# mix2_LO2.net
KiCad netlist of a schematic drawn in Altium Designer
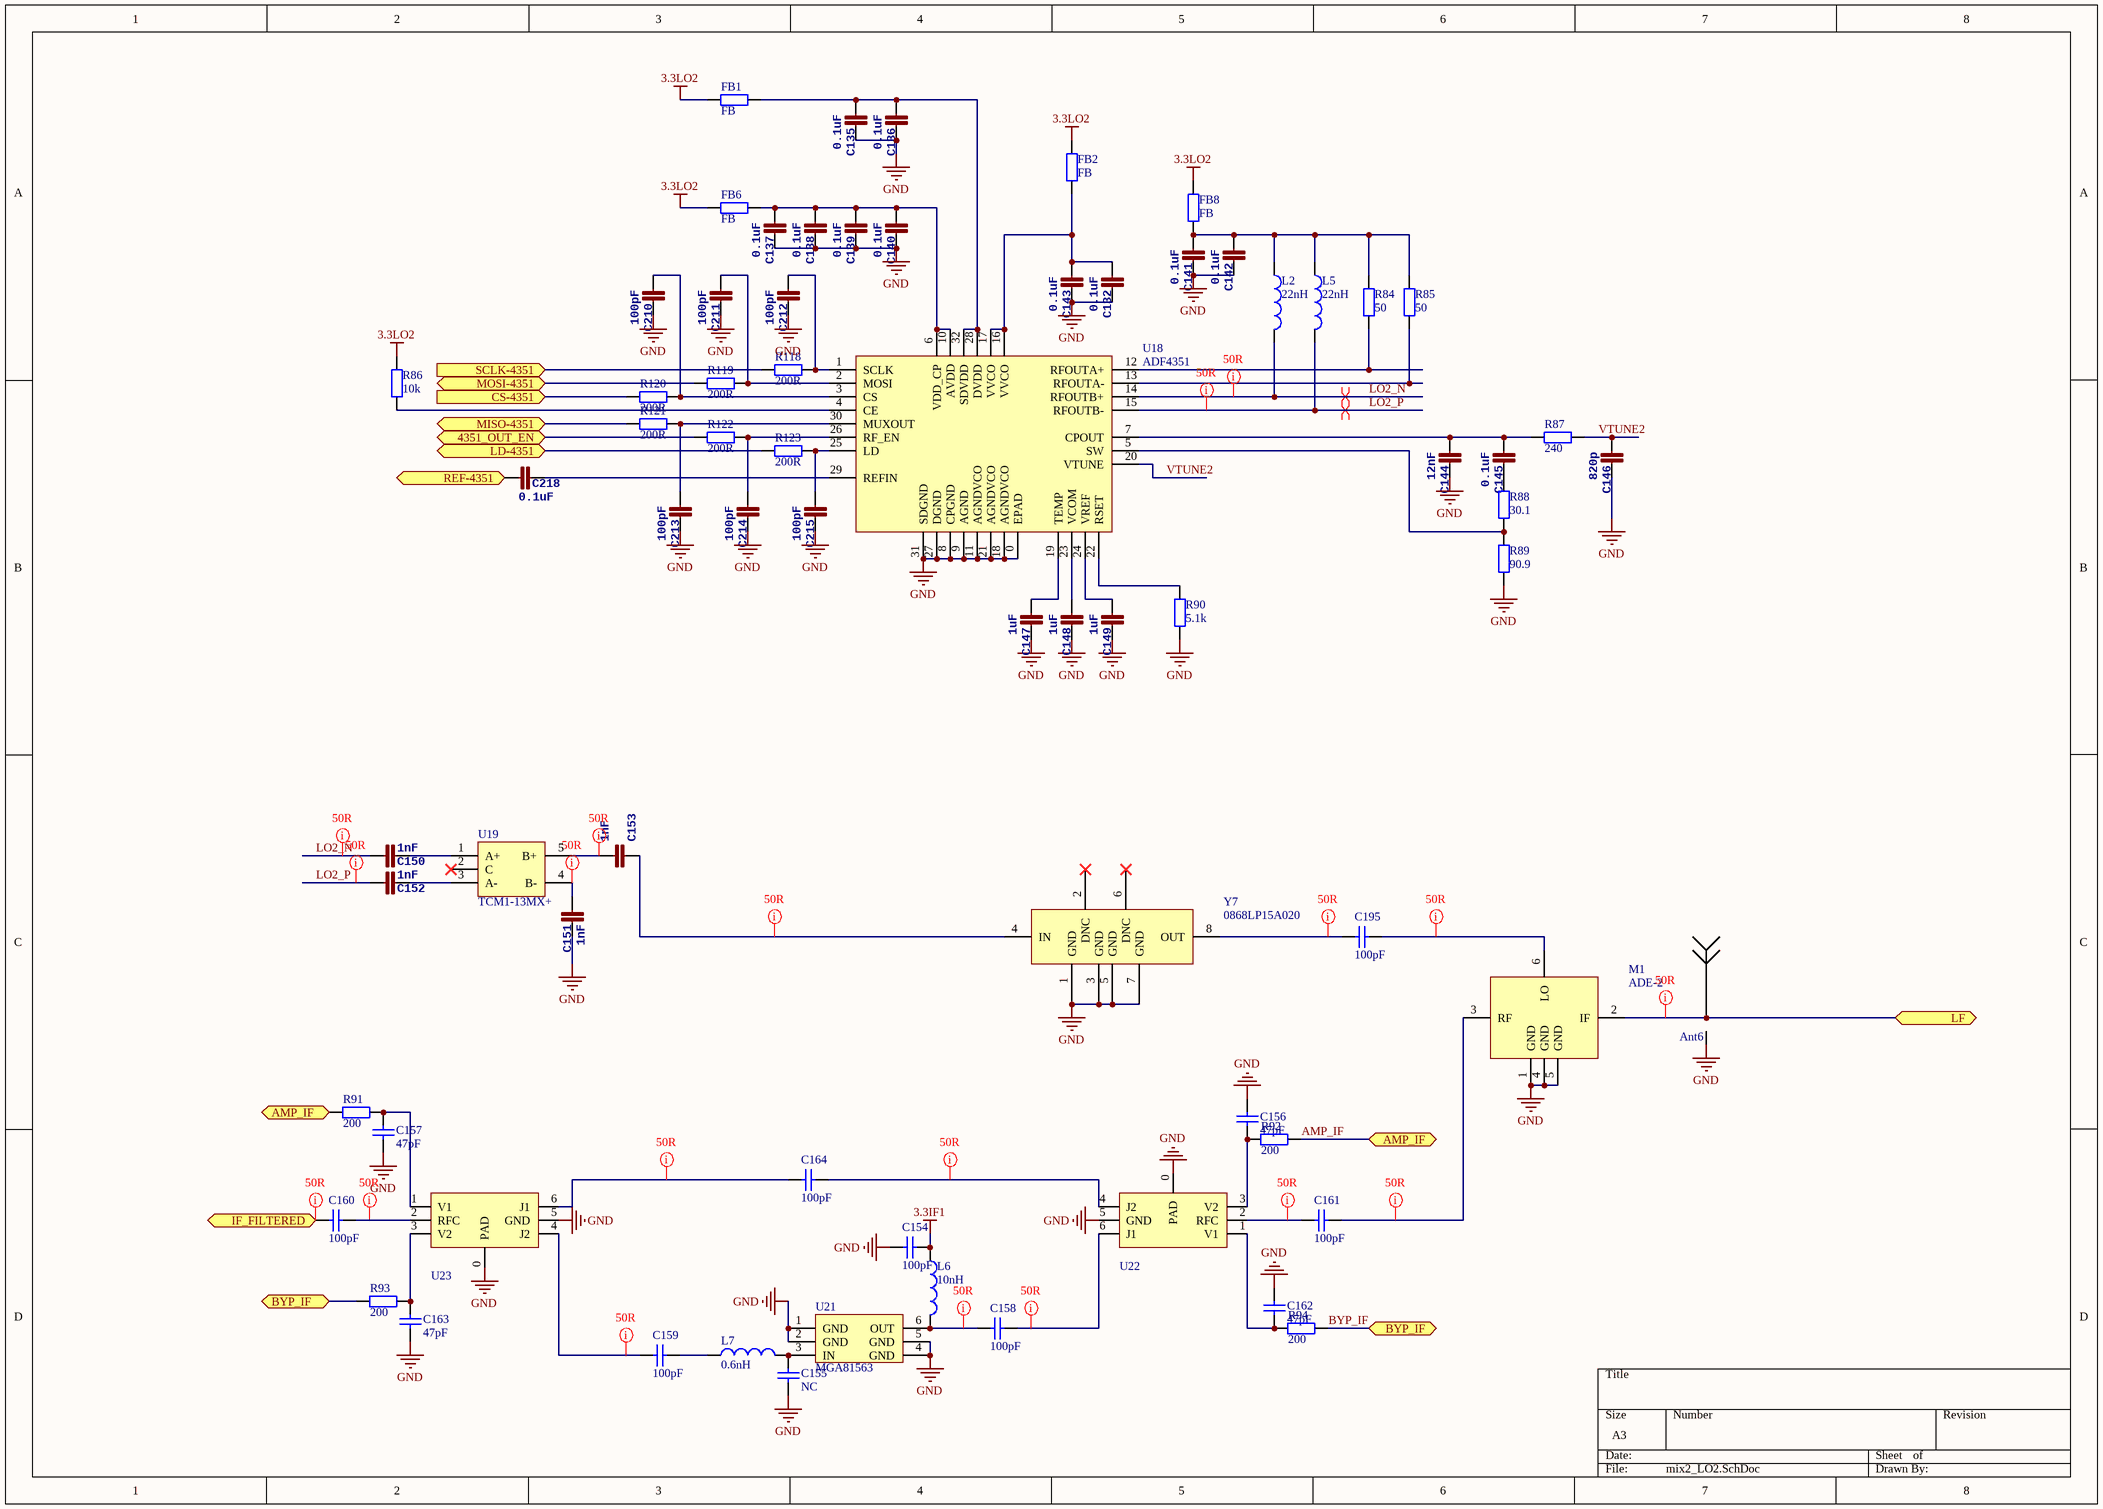
[diagram p0: mix2_LO2.SchDoc]

(export (version "E")
  (design (tool "Eeschema 10.0.6"))
  (components
    (comp (ref "Ant6") (value "Antenna") (footprint "SMA-SMT") (libsource (lib "F4SDR") (part "Antenna")))
    (comp (ref "C132")
      (value "0.1uF")
      (footprint "0402")
      (description "<b>Capacitor</b>\nStandard 0603 ceramic capacitor, and 0.1\" leaded capacitor.")
      (fields (field (name "PARTNO") "CC0402ZRY5V7BB104"))
      (libsource (lib "pixhawk2") (part "CAP0402-CAP"))
    )
    (comp (ref "C135")
      (value "0.1uF")
      (footprint "0402")
      (description "<b>Capacitor</b>\nStandard 0603 ceramic capacitor, and 0.1\" leaded capacitor.")
      (fields (field (name "PARTNO") "CC0402ZRY5V7BB104"))
      (libsource (lib "pixhawk2") (part "CAP0402-CAP"))
    )
    (comp (ref "C136")
      (value "0.1uF")
      (footprint "0402")
      (description "<b>Capacitor</b>\nStandard 0603 ceramic capacitor, and 0.1\" leaded capacitor.")
      (fields (field (name "PARTNO") "CC0402ZRY5V7BB104"))
      (libsource (lib "pixhawk2") (part "CAP0402-CAP"))
    )
    (comp (ref "C137")
      (value "0.1uF")
      (footprint "0402")
      (description "<b>Capacitor</b>\nStandard 0603 ceramic capacitor, and 0.1\" leaded capacitor.")
      (fields (field (name "PARTNO") "CC0402ZRY5V7BB104"))
      (libsource (lib "pixhawk2") (part "CAP0402-CAP"))
    )
    (comp (ref "C138")
      (value "0.1uF")
      (footprint "0402")
      (description "<b>Capacitor</b>\nStandard 0603 ceramic capacitor, and 0.1\" leaded capacitor.")
      (fields (field (name "PARTNO") "CC0402ZRY5V7BB104"))
      (libsource (lib "pixhawk2") (part "CAP0402-CAP"))
    )
    (comp (ref "C139")
      (value "0.1uF")
      (footprint "0402")
      (description "<b>Capacitor</b>\nStandard 0603 ceramic capacitor, and 0.1\" leaded capacitor.")
      (fields (field (name "PARTNO") "CC0402ZRY5V7BB104"))
      (libsource (lib "pixhawk2") (part "CAP0402-CAP"))
    )
    (comp (ref "C140")
      (value "0.1uF")
      (footprint "0402")
      (description "<b>Capacitor</b>\nStandard 0603 ceramic capacitor, and 0.1\" leaded capacitor.")
      (fields (field (name "PARTNO") "CC0402ZRY5V7BB104"))
      (libsource (lib "pixhawk2") (part "CAP0402-CAP"))
    )
    (comp (ref "C141")
      (value "0.1uF")
      (footprint "0402")
      (description "<b>Capacitor</b>\nStandard 0603 ceramic capacitor, and 0.1\" leaded capacitor.")
      (fields (field (name "PARTNO") "CC0402ZRY5V7BB104"))
      (libsource (lib "pixhawk2") (part "CAP0402-CAP"))
    )
    (comp (ref "C142")
      (value "0.1uF")
      (footprint "0402")
      (description "<b>Capacitor</b>\nStandard 0603 ceramic capacitor, and 0.1\" leaded capacitor.")
      (fields (field (name "PARTNO") "CC0402ZRY5V7BB104"))
      (libsource (lib "pixhawk2") (part "CAP0402-CAP"))
    )
    (comp (ref "C143")
      (value "0.1uF")
      (footprint "0402")
      (description "<b>Capacitor</b>\nStandard 0603 ceramic capacitor, and 0.1\" leaded capacitor.")
      (fields (field (name "PARTNO") "CC0402ZRY5V7BB104"))
      (libsource (lib "pixhawk2") (part "CAP0402-CAP"))
    )
    (comp (ref "C144")
      (value "12nF")
      (footprint "0402")
      (description "<b>Capacitor</b>\nStandard 0603 ceramic capacitor, and 0.1\" leaded capacitor.")
      (fields (field (name "PARTNO") "CC0402ZRY5V7BB104"))
      (libsource (lib "pixhawk2") (part "CAP0402-CAP"))
    )
    (comp (ref "C145")
      (value "0.1uF")
      (footprint "0402")
      (description "<b>Capacitor</b>\nStandard 0603 ceramic capacitor, and 0.1\" leaded capacitor.")
      (fields (field (name "PARTNO") "CC0402ZRY5V7BB104"))
      (libsource (lib "pixhawk2") (part "CAP0402-CAP"))
    )
    (comp (ref "C146")
      (value "820p")
      (footprint "0402")
      (description "<b>Capacitor</b>\nStandard 0603 ceramic capacitor, and 0.1\" leaded capacitor.")
      (fields (field (name "PARTNO") "CC0402ZRY5V7BB104"))
      (libsource (lib "pixhawk2") (part "CAP0402-CAP"))
    )
    (comp (ref "C147")
      (value "1uF")
      (footprint "0402")
      (description "<b>Capacitor</b>\nStandard 0603 ceramic capacitor, and 0.1\" leaded capacitor.")
      (fields (field (name "PARTNO") "CC0402ZRY5V7BB104"))
      (libsource (lib "pixhawk2") (part "CAP0402-CAP"))
    )
    (comp (ref "C148")
      (value "1uF")
      (footprint "0402")
      (description "<b>Capacitor</b>\nStandard 0603 ceramic capacitor, and 0.1\" leaded capacitor.")
      (fields (field (name "PARTNO") "CC0402ZRY5V7BB104"))
      (libsource (lib "pixhawk2") (part "CAP0402-CAP"))
    )
    (comp (ref "C149")
      (value "1uF")
      (footprint "0402")
      (description "<b>Capacitor</b>\nStandard 0603 ceramic capacitor, and 0.1\" leaded capacitor.")
      (fields (field (name "PARTNO") "CC0402ZRY5V7BB104"))
      (libsource (lib "pixhawk2") (part "CAP0402-CAP"))
    )
    (comp (ref "C150")
      (value "1nF")
      (footprint "0402")
      (description "<b>Capacitor</b>\nStandard 0603 ceramic capacitor, and 0.1\" leaded capacitor.")
      (fields (field (name "PARTNO") "CC0402ZRY5V7BB104"))
      (libsource (lib "*") (part "CAP0402-CAP"))
    )
    (comp (ref "C151")
      (value "1nF")
      (footprint "0402")
      (description "<b>Capacitor</b>\nStandard 0603 ceramic capacitor, and 0.1\" leaded capacitor.")
      (fields (field (name "PARTNO") "CC0402ZRY5V7BB104"))
      (libsource (lib "") (part "CAP0402-CAP_1"))
    )
    (comp (ref "C152")
      (value "1nF")
      (footprint "0402")
      (description "<b>Capacitor</b>\nStandard 0603 ceramic capacitor, and 0.1\" leaded capacitor.")
      (fields (field (name "PARTNO") "CC0402ZRY5V7BB104"))
      (libsource (lib "*") (part "CAP0402-CAP"))
    )
    (comp (ref "C153")
      (value "1nF")
      (footprint "0402")
      (description "<b>Capacitor</b>\nStandard 0603 ceramic capacitor, and 0.1\" leaded capacitor.")
      (fields (field (name "PARTNO") "CC0402ZRY5V7BB104"))
      (libsource (lib "*") (part "CAP0402-CAP"))
    )
    (comp (ref "C154")
      (value "100pF")
      (footprint "0402")
      (description "Capacitor")
      (fields (field (name "Comment") "Cap") (field (name "PUBLISHER") "Altium Limited"))
      (libsource (lib "RTC6705") (part "Cap"))
    )
    (comp (ref "C155")
      (value "NC")
      (footprint "0402")
      (description "Capacitor")
      (fields (field (name "Comment") "Cap") (field (name "PUBLISHER") "Altium Limited"))
      (libsource (lib "RTC6705") (part "Cap"))
    )
    (comp (ref "C156")
      (value "47pF")
      (footprint "0402")
      (description "Capacitor")
      (fields (field (name "PUBLISHER") "Altium Limited"))
      (libsource (lib "RTC6705") (part "Cap"))
    )
    (comp (ref "C157")
      (value "47pF")
      (footprint "0402")
      (description "Capacitor")
      (fields (field (name "PUBLISHER") "Altium Limited"))
      (libsource (lib "RTC6705") (part "Cap"))
    )
    (comp (ref "C158")
      (value "100pF")
      (footprint "0402")
      (description "Capacitor")
      (fields (field (name "Comment") "Cap") (field (name "PUBLISHER") "Altium Limited"))
      (libsource (lib "RTC6705") (part "Cap"))
    )
    (comp (ref "C159")
      (value "100pF")
      (footprint "0402")
      (description "Capacitor")
      (fields (field (name "Comment") "Cap") (field (name "PUBLISHER") "Altium Limited"))
      (libsource (lib "RTC6705") (part "Cap"))
    )
    (comp (ref "C160")
      (value "100pF")
      (footprint "0402")
      (description "Capacitor")
      (fields (field (name "PUBLISHER") "Altium Limited"))
      (libsource (lib "RTC6705") (part "Cap"))
    )
    (comp (ref "C161")
      (value "100pF")
      (footprint "0402")
      (description "Capacitor")
      (fields (field (name "PUBLISHER") "Altium Limited"))
      (libsource (lib "RTC6705") (part "Cap"))
    )
    (comp (ref "C162")
      (value "47pF")
      (footprint "0402")
      (description "Capacitor")
      (fields (field (name "PUBLISHER") "Altium Limited"))
      (libsource (lib "RTC6705") (part "Cap"))
    )
    (comp (ref "C163")
      (value "47pF")
      (footprint "0402")
      (description "Capacitor")
      (fields (field (name "PUBLISHER") "Altium Limited"))
      (libsource (lib "RTC6705") (part "Cap"))
    )
    (comp (ref "C164")
      (value "100pF")
      (footprint "0402")
      (description "Capacitor")
      (fields (field (name "Comment") "Cap") (field (name "PUBLISHER") "Altium Limited"))
      (libsource (lib "RTC6705") (part "Cap"))
    )
    (comp (ref "C195")
      (value "100pF")
      (footprint "0402")
      (description "Capacitor")
      (fields (field (name "PUBLISHER") "Altium Limited"))
      (libsource (lib "RTC6705") (part "Cap"))
    )
    (comp (ref "C210")
      (value "100pF")
      (footprint "0402")
      (description "<b>Capacitor</b>\nStandard 0603 ceramic capacitor, and 0.1\" leaded capacitor.")
      (fields (field (name "PARTNO") "CC0402ZRY5V7BB104"))
      (libsource (lib "pixhawk2") (part "CAP0402-CAP"))
    )
    (comp (ref "C211")
      (value "100pF")
      (footprint "0402")
      (description "<b>Capacitor</b>\nStandard 0603 ceramic capacitor, and 0.1\" leaded capacitor.")
      (fields (field (name "PARTNO") "CC0402ZRY5V7BB104"))
      (libsource (lib "pixhawk2") (part "CAP0402-CAP"))
    )
    (comp (ref "C212")
      (value "100pF")
      (footprint "0402")
      (description "<b>Capacitor</b>\nStandard 0603 ceramic capacitor, and 0.1\" leaded capacitor.")
      (fields (field (name "PARTNO") "CC0402ZRY5V7BB104"))
      (libsource (lib "pixhawk2") (part "CAP0402-CAP"))
    )
    (comp (ref "C213")
      (value "100pF")
      (footprint "0402")
      (description "<b>Capacitor</b>\nStandard 0603 ceramic capacitor, and 0.1\" leaded capacitor.")
      (fields (field (name "PARTNO") "CC0402ZRY5V7BB104"))
      (libsource (lib "pixhawk2") (part "CAP0402-CAP"))
    )
    (comp (ref "C214")
      (value "100pF")
      (footprint "0402")
      (description "<b>Capacitor</b>\nStandard 0603 ceramic capacitor, and 0.1\" leaded capacitor.")
      (fields (field (name "PARTNO") "CC0402ZRY5V7BB104"))
      (libsource (lib "pixhawk2") (part "CAP0402-CAP"))
    )
    (comp (ref "C215")
      (value "100pF")
      (footprint "0402")
      (description "<b>Capacitor</b>\nStandard 0603 ceramic capacitor, and 0.1\" leaded capacitor.")
      (fields (field (name "PARTNO") "CC0402ZRY5V7BB104"))
      (libsource (lib "pixhawk2") (part "CAP0402-CAP"))
    )
    (comp (ref "C218")
      (value "0.1uF")
      (footprint "0402")
      (description "<b>Capacitor</b>\nStandard 0603 ceramic capacitor, and 0.1\" leaded capacitor.")
      (fields (field (name "PARTNO") "CC0402ZRY5V7BB104"))
      (libsource (lib "") (part "CAP0402-CAP_1"))
    )
    (comp (ref "FB1")
      (value "FB")
      (footprint "0603")
      (description "Resistor")
      (fields (field (name "PUBLISHER") "Altium Limited"))
      (libsource (lib "Miscellaneous Devices") (part "Res2"))
    )
    (comp (ref "FB2")
      (value "FB")
      (footprint "0603")
      (description "Resistor")
      (fields (field (name "PUBLISHER") "Altium Limited"))
      (libsource (lib "") (part "Res2_1"))
    )
    (comp (ref "FB6")
      (value "FB")
      (footprint "0603")
      (description "Resistor")
      (fields (field (name "PUBLISHER") "Altium Limited"))
      (libsource (lib "Miscellaneous Devices") (part "Res2"))
    )
    (comp (ref "FB8")
      (value "FB")
      (footprint "0603")
      (description "Resistor")
      (fields (field (name "PUBLISHER") "Altium Limited"))
      (libsource (lib "") (part "Res2_1"))
    )
    (comp (ref "L2")
      (value "22nH")
      (footprint "0402")
      (description "Inductor")
      (fields (field (name "PUBLISHER") "Altium Limited"))
      (libsource (lib "Miscellaneous Devices") (part "Inductor"))
    )
    (comp (ref "L5")
      (value "22nH")
      (footprint "0402")
      (description "Inductor")
      (fields (field (name "PUBLISHER") "Altium Limited"))
      (libsource (lib "Miscellaneous Devices") (part "Inductor"))
    )
    (comp (ref "L6")
      (value "10nH")
      (footprint "0603")
      (description "Inductor")
      (fields (field (name "PUBLISHER") "Altium Limited"))
      (libsource (lib "Miscellaneous Devices") (part "Inductor"))
    )
    (comp (ref "L7")
      (value "0.6nH")
      (footprint "0402")
      (description "Inductor")
      (fields (field (name "PUBLISHER") "Altium Limited"))
      (libsource (lib "Miscellaneous Devices") (part "Inductor"))
    )
    (comp (ref "M1") (value "ADE-2") (footprint "ADE-2") (libsource (lib "F4SDR") (part "ADE-2")))
    (comp (ref "R84")
      (value "50")
      (footprint "0402")
      (description "Resistor")
      (fields (field (name "PUBLISHER") "Altium Limited"))
      (libsource (lib "") (part "Res2_1"))
    )
    (comp (ref "R85")
      (value "50")
      (footprint "0402")
      (description "Resistor")
      (fields (field (name "PUBLISHER") "Altium Limited"))
      (libsource (lib "") (part "Res2_1"))
    )
    (comp (ref "R86")
      (value "10k")
      (footprint "0402")
      (description "Resistor")
      (fields (field (name "PUBLISHER") "Altium Limited"))
      (libsource (lib "") (part "Res2_2"))
    )
    (comp (ref "R87")
      (value "240")
      (footprint "0402")
      (description "Resistor")
      (fields (field (name "PUBLISHER") "Altium Limited"))
      (libsource (lib "Miscellaneous Devices") (part "Res2"))
    )
    (comp (ref "R88")
      (value "30.1")
      (footprint "0402")
      (description "Resistor")
      (fields (field (name "PUBLISHER") "Altium Limited"))
      (libsource (lib "") (part "Res2_2"))
    )
    (comp (ref "R89")
      (value "90.9")
      (footprint "0402")
      (description "Resistor")
      (fields (field (name "PUBLISHER") "Altium Limited"))
      (libsource (lib "") (part "Res2_2"))
    )
    (comp (ref "R90")
      (value "5.1k")
      (footprint "0402")
      (description "Resistor")
      (fields (field (name "PUBLISHER") "Altium Limited"))
      (libsource (lib "") (part "Res2_2"))
    )
    (comp (ref "R91")
      (value "200")
      (footprint "0402")
      (description "Resistor")
      (fields (field (name "PUBLISHER") "Altium Limited"))
      (libsource (lib "RTC6705") (part "Res2"))
    )
    (comp (ref "R92")
      (value "200")
      (footprint "0402")
      (description "Resistor")
      (fields (field (name "PUBLISHER") "Altium Limited"))
      (libsource (lib "") (part "Res2_1"))
    )
    (comp (ref "R93")
      (value "200")
      (footprint "0402")
      (description "Resistor")
      (fields (field (name "PUBLISHER") "Altium Limited"))
      (libsource (lib "RTC6705") (part "Res2"))
    )
    (comp (ref "R94")
      (value "200")
      (footprint "0402")
      (description "Resistor")
      (fields (field (name "PUBLISHER") "Altium Limited"))
      (libsource (lib "") (part "Res2_1"))
    )
    (comp (ref "R118")
      (value "200R")
      (footprint "0402")
      (description "Resistor")
      (fields (field (name "PUBLISHER") "Altium Limited"))
      (libsource (lib "Miscellaneous Devices") (part "Res2"))
    )
    (comp (ref "R119")
      (value "200R")
      (footprint "0402")
      (description "Resistor")
      (fields (field (name "PUBLISHER") "Altium Limited"))
      (libsource (lib "Miscellaneous Devices") (part "Res2"))
    )
    (comp (ref "R120")
      (value "200R")
      (footprint "0402")
      (description "Resistor")
      (fields (field (name "PUBLISHER") "Altium Limited"))
      (libsource (lib "Miscellaneous Devices") (part "Res2"))
    )
    (comp (ref "R121")
      (value "200R")
      (footprint "0402")
      (description "Resistor")
      (fields (field (name "PUBLISHER") "Altium Limited"))
      (libsource (lib "Miscellaneous Devices") (part "Res2"))
    )
    (comp (ref "R122")
      (value "200R")
      (footprint "0402")
      (description "Resistor")
      (fields (field (name "PUBLISHER") "Altium Limited"))
      (libsource (lib "Miscellaneous Devices") (part "Res2"))
    )
    (comp (ref "R123")
      (value "200R")
      (footprint "0402")
      (description "Resistor")
      (fields (field (name "PUBLISHER") "Altium Limited"))
      (libsource (lib "Miscellaneous Devices") (part "Res2"))
    )
    (comp (ref "U18") (value "ADF4351") (footprint "ADF4351") (libsource (lib "F4SDR") (part "ADF4351")))
    (comp (ref "U19")
      (value "TCM1-13MX+")
      (footprint "TCM-63AX+")
      (libsource (lib "F4SDR") (part "TCM1-1-13M+"))
    )
    (comp (ref "U21") (value "MGA81563") (footprint "SC-70-6") (libsource (lib "F4SDR") (part "MGA81563")))
    (comp (ref "U22")
      (value "SKY13320")
      (footprint "SKY65404-31")
      (libsource (lib "F4SDR") (part "SKY13320"))
    )
    (comp (ref "U23") (value "SKY13320") (footprint "SKY65404-31") (libsource (lib "") (part "SKY13320_1")))
    (comp (ref "Y7")
      (value "0868LP15A020")
      (footprint "5515LP15A730/0868LP15A020")
      (libsource (lib "F4SDR") (part "5515LP15A730/0868LP15A020"))
    )
  )
  (nets
    (net (code "1") (name "/4351_OUT_EN") (class "Default")
      (node (ref "R122") (pin "2") (pinfunction "2_2") (pintype "passive"))
    )
    (net (code "2") (name "/AMP_IF") (class "Default")
      (node (ref "R91") (pin "1") (pinfunction "1_1") (pintype "passive"))
      (node (ref "R92") (pin "1") (pinfunction "1_1") (pintype "passive"))
    )
    (net (code "3") (name "/BYP_IF") (class "Default")
      (node (ref "R93") (pin "1") (pinfunction "1_1") (pintype "passive"))
      (node (ref "R94") (pin "1") (pinfunction "1_1") (pintype "passive"))
    )
    (net (code "4") (name "/CS-4351") (class "Default")
      (node (ref "R120") (pin "2") (pinfunction "2_2") (pintype "passive"))
    )
    (net (code "5") (name "/IF_FILTERED") (class "Default")
      (node (ref "C160") (pin "2") (pinfunction "2_2") (pintype "passive"))
    )
    (net (code "6") (name "/LD-4351") (class "Default")
      (node (ref "R123") (pin "2") (pinfunction "2_2") (pintype "passive"))
    )
    (net (code "7") (name "/LF") (class "Default")
      (node (ref "Ant6") (pin "1") (pinfunction "1_1") (pintype "passive"))
      (node (ref "M1") (pin "2") (pinfunction "IF_2") (pintype "passive"))
    )
    (net (code "8") (name "/LO2_N") (class "Default")
      (node (ref "C150") (pin "1") (pinfunction "1_1") (pintype "passive"))
      (node (ref "L2") (pin "2") (pinfunction "2_2") (pintype "passive"))
      (node (ref "U18") (pin "14") (pinfunction "RFOUTB+_14") (pintype "passive"))
    )
    (net (code "9") (name "/LO2_P") (class "Default")
      (node (ref "C152") (pin "1") (pinfunction "1_1") (pintype "passive"))
      (node (ref "L5") (pin "2") (pinfunction "2_2") (pintype "passive"))
      (node (ref "U18") (pin "15") (pinfunction "RFOUTB-_15") (pintype "passive"))
    )
    (net (code "10") (name "/MISO-4351") (class "Default")
      (node (ref "R121") (pin "2") (pinfunction "2_2") (pintype "passive"))
    )
    (net (code "11") (name "/MOSI-4351") (class "Default")
      (node (ref "R119") (pin "2") (pinfunction "2_2") (pintype "passive"))
    )
    (net (code "12") (name "/REF-4351") (class "Default")
      (node (ref "C218") (pin "1") (pinfunction "1_1") (pintype "passive"))
    )
    (net (code "13") (name "/SCLK-4351") (class "Default")
      (node (ref "R118") (pin "2") (pinfunction "2_2") (pintype "passive"))
    )
    (net (code "14") (name "/VTUNE2") (class "Default")
      (node (ref "C146") (pin "1") (pinfunction "1_1") (pintype "passive"))
      (node (ref "R87") (pin "1") (pinfunction "1_1") (pintype "passive"))
      (node (ref "U18") (pin "20") (pinfunction "VTUNE_20") (pintype "passive"))
    )
    (net (code "15") (name "3.3IF1") (class "Default")
      (node (ref "C154") (pin "2") (pinfunction "2_2") (pintype "passive"))
      (node (ref "L6") (pin "1") (pinfunction "1_1") (pintype "passive"))
    )
    (net (code "16") (name "3.3LO2") (class "Default")
      (node (ref "FB1") (pin "2") (pinfunction "2_2") (pintype "passive"))
      (node (ref "FB2") (pin "1") (pinfunction "1_1") (pintype "passive"))
      (node (ref "FB6") (pin "2") (pinfunction "2_2") (pintype "passive"))
      (node (ref "FB8") (pin "1") (pinfunction "1_1") (pintype "passive"))
      (node (ref "R86") (pin "2") (pinfunction "2_2") (pintype "passive"))
    )
    (net (code "17") (name "GND") (class "Default")
      (node (ref "Ant6") (pin "GND") (pinfunction "G_GND") (pintype "passive"))
      (node (ref "C132") (pin "2") (pinfunction "2_2") (pintype "passive"))
      (node (ref "C135") (pin "2") (pinfunction "2_2") (pintype "passive"))
      (node (ref "C136") (pin "2") (pinfunction "2_2") (pintype "passive"))
      (node (ref "C137") (pin "2") (pinfunction "2_2") (pintype "passive"))
      (node (ref "C138") (pin "2") (pinfunction "2_2") (pintype "passive"))
      (node (ref "C139") (pin "2") (pinfunction "2_2") (pintype "passive"))
      (node (ref "C140") (pin "2") (pinfunction "2_2") (pintype "passive"))
      (node (ref "C141") (pin "2") (pinfunction "2_2") (pintype "passive"))
      (node (ref "C142") (pin "2") (pinfunction "2_2") (pintype "passive"))
      (node (ref "C143") (pin "2") (pinfunction "2_2") (pintype "passive"))
      (node (ref "C144") (pin "2") (pinfunction "2_2") (pintype "passive"))
      (node (ref "C146") (pin "2") (pinfunction "2_2") (pintype "passive"))
      (node (ref "C147") (pin "2") (pinfunction "2_2") (pintype "passive"))
      (node (ref "C148") (pin "2") (pinfunction "2_2") (pintype "passive"))
      (node (ref "C149") (pin "2") (pinfunction "2_2") (pintype "passive"))
      (node (ref "C151") (pin "2") (pinfunction "2_2") (pintype "passive"))
      (node (ref "C154") (pin "1") (pinfunction "1_1") (pintype "passive"))
      (node (ref "C155") (pin "1") (pinfunction "1_1") (pintype "passive"))
      (node (ref "C156") (pin "1") (pinfunction "1_1") (pintype "passive"))
      (node (ref "C157") (pin "1") (pinfunction "1_1") (pintype "passive"))
      (node (ref "C162") (pin "1") (pinfunction "1_1") (pintype "passive"))
      (node (ref "C163") (pin "1") (pinfunction "1_1") (pintype "passive"))
      (node (ref "C210") (pin "2") (pinfunction "2_2") (pintype "passive"))
      (node (ref "C211") (pin "2") (pinfunction "2_2") (pintype "passive"))
      (node (ref "C212") (pin "2") (pinfunction "2_2") (pintype "passive"))
      (node (ref "C213") (pin "2") (pinfunction "2_2") (pintype "passive"))
      (node (ref "C214") (pin "2") (pinfunction "2_2") (pintype "passive"))
      (node (ref "C215") (pin "2") (pinfunction "2_2") (pintype "passive"))
      (node (ref "M1") (pin "1") (pinfunction "GND_1") (pintype "passive"))
      (node (ref "M1") (pin "4") (pinfunction "GND_4") (pintype "passive"))
      (node (ref "M1") (pin "5") (pinfunction "GND_5") (pintype "passive"))
      (node (ref "R89") (pin "1") (pinfunction "1_1") (pintype "passive"))
      (node (ref "R90") (pin "1") (pinfunction "1_1") (pintype "passive"))
      (node (ref "U18") (pin "0") (pinfunction "EPAD_0") (pintype "passive"))
      (node (ref "U18") (pin "11") (pinfunction "AGNDVCO_11") (pintype "passive"))
      (node (ref "U18") (pin "18") (pinfunction "AGNDVCO_18") (pintype "passive"))
      (node (ref "U18") (pin "21") (pinfunction "AGNDVCO_21") (pintype "passive"))
      (node (ref "U18") (pin "27") (pinfunction "DGND_27") (pintype "passive"))
      (node (ref "U18") (pin "31") (pinfunction "SDGND_31") (pintype "passive"))
      (node (ref "U18") (pin "8") (pinfunction "CPGND_8") (pintype "passive"))
      (node (ref "U18") (pin "9") (pinfunction "AGND_9") (pintype "passive"))
      (node (ref "U21") (pin "1") (pinfunction "GND_1") (pintype "passive"))
      (node (ref "U21") (pin "2") (pinfunction "GND_2") (pintype "passive"))
      (node (ref "U21") (pin "4") (pinfunction "GND_4") (pintype "passive"))
      (node (ref "U21") (pin "5") (pinfunction "GND_5") (pintype "passive"))
      (node (ref "U22") (pin "0") (pinfunction "PAD_0") (pintype "passive"))
      (node (ref "U22") (pin "5") (pinfunction "GND_5") (pintype "passive"))
      (node (ref "U23") (pin "0") (pinfunction "PAD_0") (pintype "passive"))
      (node (ref "U23") (pin "5") (pinfunction "GND_5") (pintype "passive"))
      (node (ref "Y7") (pin "1") (pinfunction "GND_1") (pintype "passive"))
      (node (ref "Y7") (pin "3") (pinfunction "GND_3") (pintype "passive"))
      (node (ref "Y7") (pin "5") (pinfunction "GND_5") (pintype "passive"))
      (node (ref "Y7") (pin "7") (pinfunction "GND_7") (pintype "passive"))
    )
    (net (code "18") (name "Net-(C132-Pad1)") (class "Default")
      (node (ref "C132") (pin "1") (pinfunction "1_1") (pintype "passive"))
      (node (ref "C143") (pin "1") (pinfunction "1_1") (pintype "passive"))
      (node (ref "FB2") (pin "2") (pinfunction "2_2") (pintype "passive"))
      (node (ref "U18") (pin "16") (pinfunction "VVCO_16") (pintype "passive"))
      (node (ref "U18") (pin "17") (pinfunction "VVCO_17") (pintype "passive"))
    )
    (net (code "19") (name "Net-(C141-Pad1)") (class "Default")
      (node (ref "C141") (pin "1") (pinfunction "1_1") (pintype "passive"))
      (node (ref "C142") (pin "1") (pinfunction "1_1") (pintype "passive"))
      (node (ref "FB8") (pin "2") (pinfunction "2_2") (pintype "passive"))
      (node (ref "L2") (pin "1") (pinfunction "1_1") (pintype "passive"))
      (node (ref "L5") (pin "1") (pinfunction "1_1") (pintype "passive"))
      (node (ref "R84") (pin "1") (pinfunction "1_1") (pintype "passive"))
      (node (ref "R85") (pin "1") (pinfunction "1_1") (pintype "passive"))
    )
    (net (code "20") (name "Net-(C145-Pad2)") (class "Default")
      (node (ref "C145") (pin "2") (pinfunction "2_2") (pintype "passive"))
      (node (ref "R88") (pin "2") (pinfunction "2_2") (pintype "passive"))
    )
    (net (code "21") (name "Net-(C159-Pad2)") (class "Default")
      (node (ref "C159") (pin "2") (pinfunction "2_2") (pintype "passive"))
      (node (ref "L7") (pin "1") (pinfunction "1_1") (pintype "passive"))
    )
    (net (code "22") (name "Net-(M1-LO)") (class "Default")
      (node (ref "C195") (pin "2") (pinfunction "2_2") (pintype "passive"))
      (node (ref "M1") (pin "6") (pinfunction "LO_6") (pintype "passive"))
    )
    (net (code "23") (name "Net-(M1-RF)") (class "Default")
      (node (ref "C161") (pin "2") (pinfunction "2_2") (pintype "passive"))
      (node (ref "M1") (pin "3") (pinfunction "RF_3") (pintype "passive"))
    )
    (net (code "24") (name "Net-(U18-AVDD)") (class "Default")
      (node (ref "C137") (pin "1") (pinfunction "1_1") (pintype "passive"))
      (node (ref "C138") (pin "1") (pinfunction "1_1") (pintype "passive"))
      (node (ref "C139") (pin "1") (pinfunction "1_1") (pintype "passive"))
      (node (ref "C140") (pin "1") (pinfunction "1_1") (pintype "passive"))
      (node (ref "FB6") (pin "1") (pinfunction "1_1") (pintype "passive"))
      (node (ref "U18") (pin "10") (pinfunction "AVDD_10") (pintype "passive"))
      (node (ref "U18") (pin "6") (pinfunction "VDD_CP_6") (pintype "passive"))
    )
    (net (code "25") (name "Net-(U18-CE)") (class "Default")
      (node (ref "R86") (pin "1") (pinfunction "1_1") (pintype "passive"))
      (node (ref "U18") (pin "4") (pinfunction "CE_4") (pintype "passive"))
    )
    (net (code "26") (name "Net-(U18-CPOUT)") (class "Default")
      (node (ref "C144") (pin "1") (pinfunction "1_1") (pintype "passive"))
      (node (ref "C145") (pin "1") (pinfunction "1_1") (pintype "passive"))
      (node (ref "R87") (pin "2") (pinfunction "2_2") (pintype "passive"))
      (node (ref "U18") (pin "7") (pinfunction "CPOUT_7") (pintype "passive"))
    )
    (net (code "27") (name "Net-(U18-CS)") (class "Default")
      (node (ref "C210") (pin "1") (pinfunction "1_1") (pintype "passive"))
      (node (ref "R120") (pin "1") (pinfunction "1_1") (pintype "passive"))
      (node (ref "U18") (pin "3") (pinfunction "CS_3") (pintype "passive"))
    )
    (net (code "28") (name "Net-(U18-DVDD)") (class "Default")
      (node (ref "C135") (pin "1") (pinfunction "1_1") (pintype "passive"))
      (node (ref "C136") (pin "1") (pinfunction "1_1") (pintype "passive"))
      (node (ref "FB1") (pin "1") (pinfunction "1_1") (pintype "passive"))
      (node (ref "U18") (pin "28") (pinfunction "DVDD_28") (pintype "passive"))
      (node (ref "U18") (pin "32") (pinfunction "SDVDD_32") (pintype "passive"))
    )
    (net (code "29") (name "Net-(U18-LD)") (class "Default")
      (node (ref "C215") (pin "1") (pinfunction "1_1") (pintype "passive"))
      (node (ref "R123") (pin "1") (pinfunction "1_1") (pintype "passive"))
      (node (ref "U18") (pin "25") (pinfunction "LD_25") (pintype "passive"))
    )
    (net (code "30") (name "Net-(U18-MOSI)") (class "Default")
      (node (ref "C211") (pin "1") (pinfunction "1_1") (pintype "passive"))
      (node (ref "R119") (pin "1") (pinfunction "1_1") (pintype "passive"))
      (node (ref "U18") (pin "2") (pinfunction "MOSI_2") (pintype "passive"))
    )
    (net (code "31") (name "Net-(U18-MUXOUT)") (class "Default")
      (node (ref "C213") (pin "1") (pinfunction "1_1") (pintype "passive"))
      (node (ref "R121") (pin "1") (pinfunction "1_1") (pintype "passive"))
      (node (ref "U18") (pin "30") (pinfunction "MUXOUT_30") (pintype "passive"))
    )
    (net (code "32") (name "Net-(U18-REFIN)") (class "Default")
      (node (ref "C218") (pin "2") (pinfunction "2_2") (pintype "passive"))
      (node (ref "U18") (pin "29") (pinfunction "REFIN_29") (pintype "passive"))
    )
    (net (code "33") (name "Net-(U18-RFOUTA+)") (class "Default")
      (node (ref "R84") (pin "2") (pinfunction "2_2") (pintype "passive"))
      (node (ref "U18") (pin "12") (pinfunction "RFOUTA+_12") (pintype "passive"))
    )
    (net (code "34") (name "Net-(U18-RFOUTA-)") (class "Default")
      (node (ref "R85") (pin "2") (pinfunction "2_2") (pintype "passive"))
      (node (ref "U18") (pin "13") (pinfunction "RFOUTA-_13") (pintype "passive"))
    )
    (net (code "35") (name "Net-(U18-RF_EN)") (class "Default")
      (node (ref "C214") (pin "1") (pinfunction "1_1") (pintype "passive"))
      (node (ref "R122") (pin "1") (pinfunction "1_1") (pintype "passive"))
      (node (ref "U18") (pin "26") (pinfunction "RF_EN_26") (pintype "passive"))
    )
    (net (code "36") (name "Net-(U18-RSET)") (class "Default")
      (node (ref "R90") (pin "2") (pinfunction "2_2") (pintype "passive"))
      (node (ref "U18") (pin "22") (pinfunction "RSET_22") (pintype "passive"))
    )
    (net (code "37") (name "Net-(U18-SCLK)") (class "Default")
      (node (ref "C212") (pin "1") (pinfunction "1_1") (pintype "passive"))
      (node (ref "R118") (pin "1") (pinfunction "1_1") (pintype "passive"))
      (node (ref "U18") (pin "1") (pinfunction "SCLK_1") (pintype "passive"))
    )
    (net (code "38") (name "Net-(U18-SW)") (class "Default")
      (node (ref "R88") (pin "1") (pinfunction "1_1") (pintype "passive"))
      (node (ref "R89") (pin "2") (pinfunction "2_2") (pintype "passive"))
      (node (ref "U18") (pin "5") (pinfunction "SW_5") (pintype "passive"))
    )
    (net (code "39") (name "Net-(U18-TEMP)") (class "Default")
      (node (ref "C147") (pin "1") (pinfunction "1_1") (pintype "passive"))
      (node (ref "U18") (pin "19") (pinfunction "TEMP_19") (pintype "passive"))
    )
    (net (code "40") (name "Net-(U18-VCOM)") (class "Default")
      (node (ref "C148") (pin "1") (pinfunction "1_1") (pintype "passive"))
      (node (ref "U18") (pin "23") (pinfunction "VCOM_23") (pintype "passive"))
    )
    (net (code "41") (name "Net-(U18-VREF)") (class "Default")
      (node (ref "C149") (pin "1") (pinfunction "1_1") (pintype "passive"))
      (node (ref "U18") (pin "24") (pinfunction "VREF_24") (pintype "passive"))
    )
    (net (code "42") (name "Net-(U19-A+)") (class "Default")
      (node (ref "C150") (pin "2") (pinfunction "2_2") (pintype "passive"))
      (node (ref "U19") (pin "1") (pinfunction "A+_1") (pintype "passive"))
    )
    (net (code "43") (name "Net-(U19-A-)") (class "Default")
      (node (ref "C152") (pin "2") (pinfunction "2_2") (pintype "passive"))
      (node (ref "U19") (pin "3") (pinfunction "A-_3") (pintype "passive"))
    )
    (net (code "44") (name "Net-(U19-B+)") (class "Default")
      (node (ref "C153") (pin "1") (pinfunction "1_1") (pintype "passive"))
      (node (ref "U19") (pin "5") (pinfunction "B+_5") (pintype "passive"))
    )
    (net (code "45") (name "Net-(U19-B-)") (class "Default")
      (node (ref "C151") (pin "1") (pinfunction "1_1") (pintype "passive"))
      (node (ref "U19") (pin "4") (pinfunction "B-_4") (pintype "passive"))
    )
    (net (code "46") (name "Net-(U21-IN)") (class "Default")
      (node (ref "C155") (pin "2") (pinfunction "2_2") (pintype "passive"))
      (node (ref "L7") (pin "2") (pinfunction "2_2") (pintype "passive"))
      (node (ref "U21") (pin "3") (pinfunction "IN_3") (pintype "passive"))
    )
    (net (code "47") (name "Net-(U21-OUT)") (class "Default")
      (node (ref "C158") (pin "1") (pinfunction "1_1") (pintype "passive"))
      (node (ref "L6") (pin "2") (pinfunction "2_2") (pintype "passive"))
      (node (ref "U21") (pin "6") (pinfunction "OUT_6") (pintype "passive"))
    )
    (net (code "48") (name "Net-(U22-J1)") (class "Default")
      (node (ref "C158") (pin "2") (pinfunction "2_2") (pintype "passive"))
      (node (ref "U22") (pin "6") (pinfunction "J1_6") (pintype "passive"))
    )
    (net (code "49") (name "Net-(U22-J2)") (class "Default")
      (node (ref "C164") (pin "2") (pinfunction "2_2") (pintype "passive"))
      (node (ref "U22") (pin "4") (pinfunction "J2_4") (pintype "passive"))
    )
    (net (code "50") (name "Net-(U22-RFC)") (class "Default")
      (node (ref "C161") (pin "1") (pinfunction "1_1") (pintype "passive"))
      (node (ref "U22") (pin "2") (pinfunction "RFC_2") (pintype "passive"))
    )
    (net (code "51") (name "Net-(U22-V1)") (class "Default")
      (node (ref "C162") (pin "2") (pinfunction "2_2") (pintype "passive"))
      (node (ref "R94") (pin "2") (pinfunction "2_2") (pintype "passive"))
      (node (ref "U22") (pin "1") (pinfunction "V1_1") (pintype "passive"))
    )
    (net (code "52") (name "Net-(U22-V2)") (class "Default")
      (node (ref "C156") (pin "2") (pinfunction "2_2") (pintype "passive"))
      (node (ref "R92") (pin "2") (pinfunction "2_2") (pintype "passive"))
      (node (ref "U22") (pin "3") (pinfunction "V2_3") (pintype "passive"))
    )
    (net (code "53") (name "Net-(U23-J1)") (class "Default")
      (node (ref "C164") (pin "1") (pinfunction "1_1") (pintype "passive"))
      (node (ref "U23") (pin "6") (pinfunction "J1_6") (pintype "passive"))
    )
    (net (code "54") (name "Net-(U23-J2)") (class "Default")
      (node (ref "C159") (pin "1") (pinfunction "1_1") (pintype "passive"))
      (node (ref "U23") (pin "4") (pinfunction "J2_4") (pintype "passive"))
    )
    (net (code "55") (name "Net-(U23-RFC)") (class "Default")
      (node (ref "C160") (pin "1") (pinfunction "1_1") (pintype "passive"))
      (node (ref "U23") (pin "2") (pinfunction "RFC_2") (pintype "passive"))
    )
    (net (code "56") (name "Net-(U23-V1)") (class "Default")
      (node (ref "C157") (pin "2") (pinfunction "2_2") (pintype "passive"))
      (node (ref "R91") (pin "2") (pinfunction "2_2") (pintype "passive"))
      (node (ref "U23") (pin "1") (pinfunction "V1_1") (pintype "passive"))
    )
    (net (code "57") (name "Net-(U23-V2)") (class "Default")
      (node (ref "C163") (pin "2") (pinfunction "2_2") (pintype "passive"))
      (node (ref "R93") (pin "2") (pinfunction "2_2") (pintype "passive"))
      (node (ref "U23") (pin "3") (pinfunction "V2_3") (pintype "passive"))
    )
    (net (code "58") (name "Net-(Y7-IN)") (class "Default")
      (node (ref "C153") (pin "2") (pinfunction "2_2") (pintype "passive"))
      (node (ref "Y7") (pin "4") (pinfunction "IN_4") (pintype "passive"))
    )
    (net (code "59") (name "Net-(Y7-OUT)") (class "Default")
      (node (ref "C195") (pin "1") (pinfunction "1_1") (pintype "passive"))
      (node (ref "Y7") (pin "8") (pinfunction "OUT_8") (pintype "passive"))
    )
    (net (code "60") (name "unconnected-(U19-C-Pad2)") (class "Default")
      (node (ref "U19") (pin "2") (pinfunction "C_2") (pintype "passive+no_connect"))
    )
    (net (code "61") (name "unconnected-(Y7-DNC-Pad2)") (class "Default")
      (node (ref "Y7") (pin "2") (pinfunction "DNC_2") (pintype "passive+no_connect"))
    )
    (net (code "62") (name "unconnected-(Y7-DNC-Pad6)") (class "Default")
      (node (ref "Y7") (pin "6") (pinfunction "DNC_6") (pintype "passive+no_connect"))
    )
  )
)
